# Sheet1.net
KiCad netlist of a schematic drawn in Altium Designer
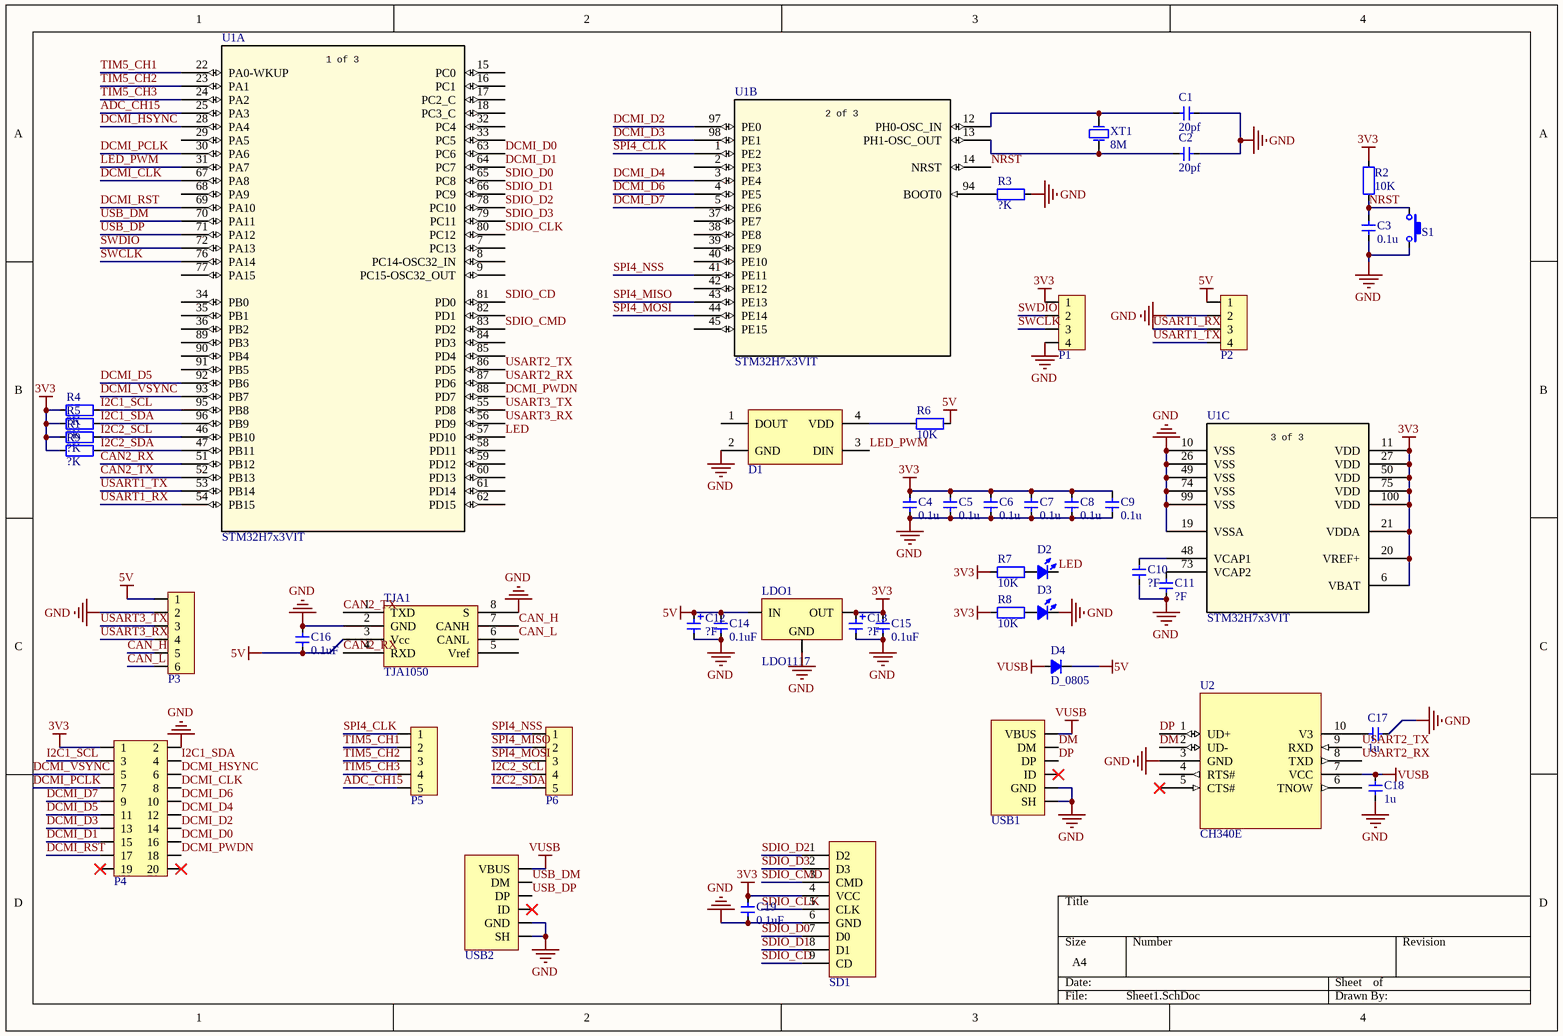
[diagram p0: Sheet1.SchDoc]

(export (version "E")
  (design (tool "Eeschema 10.0.6"))
  (components
    (comp (ref "C1")
      (value "20pf")
      (footprint "PCB_PassiveCap:CAP_0603")
      (description "Capacitor")
      (fields (field (name "Comment") "Cap_0603"))
      (libsource (lib "SCH_Passive") (part "Cap_0603"))
    )
    (comp (ref "C2")
      (value "20pf")
      (footprint "PCB_PassiveCap:CAP_0603")
      (description "Capacitor")
      (fields (field (name "Comment") "Cap_0603"))
      (libsource (lib "SCH_Passive") (part "Cap_0603"))
    )
    (comp (ref "C3")
      (value "0.1u")
      (footprint "PCB_PassiveCap:CAP_0603")
      (description "Capacitor")
      (fields (field (name "Comment") "Cap_0603"))
      (libsource (lib "SCH_Passive") (part "Cap_0603"))
    )
    (comp (ref "C4")
      (value "0.1u")
      (footprint "PCB_PassiveCap:CAP_0603")
      (description "Capacitor")
      (fields (field (name "Comment") "Cap_0603"))
      (libsource (lib "SCH_Passive") (part "Cap_0603"))
    )
    (comp (ref "C5")
      (value "0.1u")
      (footprint "PCB_PassiveCap:CAP_0603")
      (description "Capacitor")
      (fields (field (name "Comment") "Cap_0603"))
      (libsource (lib "SCH_Passive") (part "Cap_0603"))
    )
    (comp (ref "C6")
      (value "0.1u")
      (footprint "PCB_PassiveCap:CAP_0603")
      (description "Capacitor")
      (fields (field (name "Comment") "Cap_0603"))
      (libsource (lib "SCH_Passive") (part "Cap_0603"))
    )
    (comp (ref "C7")
      (value "0.1u")
      (footprint "PCB_PassiveCap:CAP_0603")
      (description "Capacitor")
      (fields (field (name "Comment") "Cap_0603"))
      (libsource (lib "SCH_Passive") (part "Cap_0603"))
    )
    (comp (ref "C8")
      (value "0.1u")
      (footprint "PCB_PassiveCap:CAP_0603")
      (description "Capacitor")
      (fields (field (name "Comment") "Cap_0603"))
      (libsource (lib "SCH_Passive") (part "Cap_0603"))
    )
    (comp (ref "C9")
      (value "0.1u")
      (footprint "PCB_PassiveCap:CAP_0603")
      (description "Capacitor")
      (fields (field (name "Comment") "Cap_0603"))
      (libsource (lib "SCH_Passive") (part "Cap_0603"))
    )
    (comp (ref "C10")
      (value "?F")
      (footprint "PCB_PassiveCap:CAP_0603")
      (description "Capacitor")
      (fields (field (name "Comment") "Cap_0603"))
      (libsource (lib "SCH_Passive") (part "Cap_0603"))
    )
    (comp (ref "C11")
      (value "?F")
      (footprint "PCB_PassiveCap:CAP_0603")
      (description "Capacitor")
      (fields (field (name "Comment") "Cap_0603"))
      (libsource (lib "SCH_Passive") (part "Cap_0603"))
    )
    (comp (ref "C12")
      (value "?F")
      (footprint "PCB_PassiveCap:CAP_TAN_A1206")
      (description "Capacitor")
      (fields (field (name "Comment") "Cap_Tan_1206"))
      (libsource (lib "SCH_Passive") (part "Cap_Tan_1206"))
    )
    (comp (ref "C13")
      (value "?F")
      (footprint "PCB_PassiveCap:CAP_TAN_A1206")
      (description "Capacitor")
      (fields (field (name "Comment") "Cap_Tan_1206"))
      (libsource (lib "SCH_Passive") (part "Cap_Tan_1206"))
    )
    (comp (ref "C14")
      (value "0.1uF")
      (footprint "PCB_PassiveCap:CAP_0603")
      (description "Capacitor")
      (fields (field (name "Comment") "Cap_0603"))
      (libsource (lib "SCH_Passive") (part "Cap_0603"))
    )
    (comp (ref "C15")
      (value "0.1uF")
      (footprint "PCB_PassiveCap:CAP_0603")
      (description "Capacitor")
      (fields (field (name "Comment") "Cap_0603"))
      (libsource (lib "SCH_Passive") (part "Cap_0603"))
    )
    (comp (ref "C16")
      (value "0.1uF")
      (footprint "PCB_PassiveCap:CAP_0603")
      (description "Capacitor")
      (fields (field (name "Comment") "Cap_0603"))
      (libsource (lib "SCH_Passive") (part "Cap_0603"))
    )
    (comp (ref "C17")
      (value "1u")
      (footprint "PCB_PassiveCap:CAP_0603")
      (description "Capacitor")
      (fields (field (name "Comment") "Cap_0603"))
      (libsource (lib "SCH_Passive") (part "Cap_0603"))
    )
    (comp (ref "C18")
      (value "1u")
      (footprint "PCB_PassiveCap:CAP_0603")
      (description "Capacitor")
      (fields (field (name "Comment") "Cap_0603"))
      (libsource (lib "SCH_Passive") (part "Cap_0603"))
    )
    (comp (ref "C19")
      (value "0.1uF")
      (footprint "PCB_PassiveCap:CAP_0603")
      (description "Capacitor")
      (fields (field (name "Comment") "Cap_0603"))
      (libsource (lib "SCH_Passive") (part "Cap_0603"))
    )
    (comp (ref "D1")
      (value "LED_3535_SK6812")
      (footprint "PCB_ActiveLED:LED_3535_4P")
      (description "LED")
      (libsource (lib "SCH_Active") (part "LED_3535_SK6812"))
    )
    (comp (ref "D2")
      (value "LED_0805")
      (footprint "PCB_ActiveLED:LED_0805_RED")
      (description "LED")
      (libsource (lib "SCH_Active") (part "LED_0805"))
    )
    (comp (ref "D3")
      (value "LED_0805")
      (footprint "PCB_ActiveLED:LED_0805_RED")
      (description "LED")
      (libsource (lib "SCH_Active") (part "LED_0805"))
    )
    (comp (ref "D4")
      (value "D_0805")
      (footprint "LED_0805_YELLOW")
      (libsource (lib "SCH_Active") (part "D_0805"))
    )
    (comp (ref "LDO1")
      (value "LDO1117")
      (footprint "PCB_IntegratedCircuit:SOT223-3")
      (description "Power")
      (libsource (lib "SCH_IntegratedCircuit") (part "LDO1117"))
    )
    (comp (ref "P1")
      (value "HDR1x4_2.54")
      (footprint "PCB_ConnectorHDR:HDR1x4_2.54_180")
      (description "Header")
      (libsource (lib "SCH_ConnectorHDR") (part "HDR1x4_2.54"))
    )
    (comp (ref "P2")
      (value "HDR1x4_2.54")
      (footprint "PCB_ConnectorHDR:HDR1x4_2.54_180")
      (description "Header")
      (libsource (lib "SCH_ConnectorHDR") (part "HDR1x4_2.54"))
    )
    (comp (ref "P3")
      (value "HDR1x6_2.54")
      (footprint "PCB_ConnectorHDR:HDR1X6_2.54_180")
      (description "Header")
      (libsource (lib "SCH_ConnectorHDR") (part "HDR1x6_2.54"))
    )
    (comp (ref "P4")
      (value "HDR2x10_2.54")
      (footprint "PCB_ConnectorHDR:HDR2X10_2.54_180")
      (description "Header")
      (libsource (lib "SCH_ConnectorHDR") (part "HDR2x10_2.54"))
    )
    (comp (ref "P5")
      (value "HDR1x5_2.54")
      (footprint "PCB_ConnectorHDR:HDR1X5_2.54_180")
      (description "Header")
      (libsource (lib "SCH_ConnectorHDR") (part "HDR1x5_2.54"))
    )
    (comp (ref "P6")
      (value "HDR1x5_2.54")
      (footprint "PCB_ConnectorHDR:HDR1X5_2.54_180")
      (description "Header")
      (libsource (lib "SCH_ConnectorHDR") (part "HDR1x5_2.54"))
    )
    (comp (ref "R1")
      (value "?K")
      (footprint "PCB_PassiveRes:RES_0603")
      (description "Resistor")
      (fields (field (name "Comment") "Res_0603"))
      (libsource (lib "SCH_Passive") (part "Res_0603"))
    )
    (comp (ref "R2")
      (value "10K")
      (footprint "PCB_PassiveRes:RES_0603")
      (description "Resistor")
      (fields (field (name "Comment") "Res_0603"))
      (libsource (lib "") (part "Res_0603_1"))
    )
    (comp (ref "R3")
      (value "?K")
      (footprint "PCB_PassiveRes:RES_0603")
      (description "Resistor")
      (fields (field (name "Comment") "Res_0603"))
      (libsource (lib "SCH_Passive") (part "Res_0603"))
    )
    (comp (ref "R4")
      (value "?K")
      (footprint "PCB_PassiveRes:RES_0603")
      (description "Resistor")
      (fields (field (name "Comment") "Res_0603"))
      (libsource (lib "SCH_Passive") (part "Res_0603"))
    )
    (comp (ref "R5")
      (value "?K")
      (footprint "PCB_PassiveRes:RES_0603")
      (description "Resistor")
      (fields (field (name "Comment") "Res_0603"))
      (libsource (lib "SCH_Passive") (part "Res_0603"))
    )
    (comp (ref "R6")
      (value "10K")
      (footprint "PCB_PassiveRes:RES_0603")
      (description "Resistor")
      (fields (field (name "Comment") "Res_0603"))
      (libsource (lib "SCH_Passive") (part "Res_0603"))
    )
    (comp (ref "R7")
      (value "10K")
      (footprint "PCB_PassiveRes:RES_0603")
      (description "Resistor")
      (fields (field (name "Comment") "Res_0603"))
      (libsource (lib "SCH_Passive") (part "Res_0603"))
    )
    (comp (ref "R8")
      (value "10K")
      (footprint "PCB_PassiveRes:RES_0603")
      (description "Resistor")
      (fields (field (name "Comment") "Res_0603"))
      (libsource (lib "SCH_Passive") (part "Res_0603"))
    )
    (comp (ref "R9")
      (value "?K")
      (footprint "PCB_PassiveRes:RES_0603")
      (description "Resistor")
      (fields (field (name "Comment") "Res_0603"))
      (libsource (lib "SCH_Passive") (part "Res_0603"))
    )
    (comp (ref "S1")
      (value "ButtonTACT_3x4x2_180")
      (footprint "PCB_Switch:ButtonTACT_3x4x2_180H")
      (description "Button")
      (libsource (lib "SCH_Switch") (part "ButtonTACT_3x4x2_180"))
    )
    (comp (ref "SD1")
      (value "SD_Card_TF")
      (footprint "PCB_SDCard:SD_Card_TF")
      (description "SD")
      (libsource (lib "SCH_SDCard") (part "SD_Card_TF"))
    )
    (comp (ref "TJA1")
      (value "TJA1050")
      (footprint "SOP_E150_8")
      (libsource (lib "SCH_IntegratedCircuit") (part "TJA1050"))
    )
    (comp (ref "U1")
      (value "STM32H7x3VIT")
      (footprint "STM32H743VIT")
      (description "Imported")
      (fields
        (field (name "MANUFACTURER_PART_NUMBER") "stm32h7x3vit")
        (field (name "COPYRIGHT") "Copyright (C) 2016 Accelerated Designs. All rights reserved")
      )
      (libsource (lib "SCH_IntegratedCircuit") (part "STM32H7x3VIT"))
    )
    (comp (ref "U2")
      (value "CH340E")
      (footprint "MSOP10")
      (description "USB to TTL Serial / UART")
      (libsource (lib "*") (part "CH340E"))
    )
    (comp (ref "USB1")
      (value "USB_Micro")
      (footprint "PCB_USB:USB_Micro-AB")
      (description "USB")
      (libsource (lib "SCH_USB") (part "USB_Micro"))
    )
    (comp (ref "USB2")
      (value "USB_Micro")
      (footprint "PCB_USB:USB_Micro-AB")
      (description "USB")
      (libsource (lib "SCH_USB") (part "USB_Micro"))
    )
    (comp (ref "XT1")
      (value "8M")
      (footprint "PCB_Oscillator:XT_5032_2")
      (description "Crystal Oscillator")
      (fields (field (name "Comment") "XTAL_5032_2P"))
      (libsource (lib "SCH_Oscillator") (part "XTAL_5032_2P"))
    )
  )
  (nets
    (net (code "1") (name "/ADC_CH15") (class "Default")
      (node (ref "P5") (pin "5") (pinfunction "5_5") (pintype "passive"))
      (node (ref "U1") (pin "25") (pinfunction "PA3_25") (pintype "bidirectional"))
    )
    (net (code "2") (name "/CAN2_RX") (class "Default")
      (node (ref "TJA1") (pin "4") (pinfunction "RXD_4") (pintype "passive"))
      (node (ref "U1") (pin "51") (pinfunction "PB12_51") (pintype "bidirectional"))
    )
    (net (code "3") (name "/CAN2_TX") (class "Default")
      (node (ref "TJA1") (pin "1") (pinfunction "TXD_1") (pintype "passive"))
      (node (ref "U1") (pin "52") (pinfunction "PB13_52") (pintype "bidirectional"))
    )
    (net (code "4") (name "/CAN_H") (class "Default")
      (node (ref "P3") (pin "5") (pinfunction "5_5") (pintype "passive"))
      (node (ref "TJA1") (pin "7") (pinfunction "CANH_7") (pintype "passive"))
    )
    (net (code "5") (name "/CAN_L") (class "Default")
      (node (ref "P3") (pin "6") (pinfunction "6_6") (pintype "passive"))
      (node (ref "TJA1") (pin "6") (pinfunction "CANL_6") (pintype "passive"))
    )
    (net (code "6") (name "/DCMI_CLK") (class "Default")
      (node (ref "P4") (pin "8") (pinfunction "8_8") (pintype "passive"))
      (node (ref "U1") (pin "67") (pinfunction "PA8_67") (pintype "bidirectional"))
    )
    (net (code "7") (name "/DCMI_D0") (class "Default")
      (node (ref "P4") (pin "16") (pinfunction "16_16") (pintype "passive"))
      (node (ref "U1") (pin "63") (pinfunction "PC6_63") (pintype "bidirectional"))
    )
    (net (code "8") (name "/DCMI_D1") (class "Default")
      (node (ref "P4") (pin "15") (pinfunction "15_15") (pintype "passive"))
      (node (ref "U1") (pin "64") (pinfunction "PC7_64") (pintype "bidirectional"))
    )
    (net (code "9") (name "/DCMI_D2") (class "Default")
      (node (ref "P4") (pin "14") (pinfunction "14_14") (pintype "passive"))
      (node (ref "U1") (pin "97") (pinfunction "PE0_97") (pintype "bidirectional"))
    )
    (net (code "10") (name "/DCMI_D3") (class "Default")
      (node (ref "P4") (pin "13") (pinfunction "13_13") (pintype "passive"))
      (node (ref "U1") (pin "98") (pinfunction "PE1_98") (pintype "bidirectional"))
    )
    (net (code "11") (name "/DCMI_D4") (class "Default")
      (node (ref "P4") (pin "12") (pinfunction "12_12") (pintype "passive"))
      (node (ref "U1") (pin "3") (pinfunction "PE4_3") (pintype "bidirectional"))
    )
    (net (code "12") (name "/DCMI_D5") (class "Default")
      (node (ref "P4") (pin "11") (pinfunction "11_11") (pintype "passive"))
      (node (ref "U1") (pin "92") (pinfunction "PB6_92") (pintype "bidirectional"))
    )
    (net (code "13") (name "/DCMI_D6") (class "Default")
      (node (ref "P4") (pin "10") (pinfunction "10_10") (pintype "passive"))
      (node (ref "U1") (pin "4") (pinfunction "PE5_4") (pintype "bidirectional"))
    )
    (net (code "14") (name "/DCMI_D7") (class "Default")
      (node (ref "P4") (pin "9") (pinfunction "9_9") (pintype "passive"))
      (node (ref "U1") (pin "5") (pinfunction "PE6_5") (pintype "bidirectional"))
    )
    (net (code "15") (name "/DCMI_HSYNC") (class "Default")
      (node (ref "P4") (pin "6") (pinfunction "6_6") (pintype "passive"))
      (node (ref "U1") (pin "28") (pinfunction "PA4_28") (pintype "bidirectional"))
    )
    (net (code "16") (name "/DCMI_PCLK") (class "Default")
      (node (ref "P4") (pin "7") (pinfunction "7_7") (pintype "passive"))
      (node (ref "U1") (pin "30") (pinfunction "PA6_30") (pintype "bidirectional"))
    )
    (net (code "17") (name "/DCMI_PWDN") (class "Default")
      (node (ref "P4") (pin "18") (pinfunction "18_18") (pintype "passive"))
      (node (ref "U1") (pin "88") (pinfunction "PD7_88") (pintype "bidirectional"))
    )
    (net (code "18") (name "/DCMI_RST") (class "Default")
      (node (ref "P4") (pin "17") (pinfunction "17_17") (pintype "passive"))
      (node (ref "U1") (pin "69") (pinfunction "PA10_69") (pintype "bidirectional"))
    )
    (net (code "19") (name "/DCMI_VSYNC") (class "Default")
      (node (ref "P4") (pin "5") (pinfunction "5_5") (pintype "passive"))
      (node (ref "U1") (pin "93") (pinfunction "PB7_93") (pintype "bidirectional"))
    )
    (net (code "20") (name "/DM") (class "Default")
      (node (ref "U2") (pin "2") (pinfunction "UD-_2") (pintype "bidirectional"))
      (node (ref "USB1") (pin "2") (pinfunction "DM_2") (pintype "passive"))
    )
    (net (code "21") (name "/DP") (class "Default")
      (node (ref "U2") (pin "1") (pinfunction "UD+_1") (pintype "bidirectional"))
      (node (ref "USB1") (pin "3") (pinfunction "DP_3") (pintype "passive"))
    )
    (net (code "22") (name "/I2C1_SCL") (class "Default")
      (node (ref "P4") (pin "3") (pinfunction "3_3") (pintype "passive"))
      (node (ref "R4") (pin "2") (pinfunction "2_2") (pintype "passive"))
      (node (ref "U1") (pin "95") (pinfunction "PB8_95") (pintype "bidirectional"))
    )
    (net (code "23") (name "/I2C1_SDA") (class "Default")
      (node (ref "P4") (pin "4") (pinfunction "4_4") (pintype "passive"))
      (node (ref "R5") (pin "2") (pinfunction "2_2") (pintype "passive"))
      (node (ref "U1") (pin "96") (pinfunction "PB9_96") (pintype "bidirectional"))
    )
    (net (code "24") (name "/I2C2_SCL") (class "Default")
      (node (ref "P6") (pin "4") (pinfunction "4_4") (pintype "passive"))
      (node (ref "R1") (pin "2") (pinfunction "2_2") (pintype "passive"))
      (node (ref "U1") (pin "46") (pinfunction "PB10_46") (pintype "bidirectional"))
    )
    (net (code "25") (name "/I2C2_SDA") (class "Default")
      (node (ref "P6") (pin "5") (pinfunction "5_5") (pintype "passive"))
      (node (ref "R9") (pin "2") (pinfunction "2_2") (pintype "passive"))
      (node (ref "U1") (pin "47") (pinfunction "PB11_47") (pintype "bidirectional"))
    )
    (net (code "26") (name "/LED") (class "Default")
      (node (ref "D2") (pin "2") (pinfunction "K_2") (pintype "passive"))
      (node (ref "U1") (pin "57") (pinfunction "PD10_57") (pintype "bidirectional"))
    )
    (net (code "27") (name "/LED_PWM") (class "Default")
      (node (ref "D1") (pin "3") (pinfunction "DIN_3") (pintype "passive"))
      (node (ref "U1") (pin "31") (pinfunction "PA7_31") (pintype "bidirectional"))
    )
    (net (code "28") (name "/NRST") (class "Default")
      (node (ref "C3") (pin "2") (pinfunction "2_2") (pintype "passive"))
      (node (ref "R2") (pin "2") (pinfunction "2_2") (pintype "passive"))
      (node (ref "S1") (pin "1") (pinfunction "1_1") (pintype "passive"))
      (node (ref "U1") (pin "14") (pinfunction "NRST_14") (pintype "bidirectional"))
    )
    (net (code "29") (name "/SDIO_CD") (class "Default")
      (node (ref "SD1") (pin "9") (pinfunction "CD_9") (pintype "passive"))
      (node (ref "U1") (pin "81") (pinfunction "PD0_81") (pintype "bidirectional"))
    )
    (net (code "30") (name "/SDIO_CLK") (class "Default")
      (node (ref "SD1") (pin "5") (pinfunction "CLK_5") (pintype "passive"))
      (node (ref "U1") (pin "80") (pinfunction "PC12_80") (pintype "bidirectional"))
    )
    (net (code "31") (name "/SDIO_CMD") (class "Default")
      (node (ref "SD1") (pin "3") (pinfunction "CMD_3") (pintype "passive"))
      (node (ref "U1") (pin "83") (pinfunction "PD2_83") (pintype "bidirectional"))
    )
    (net (code "32") (name "/SDIO_D0") (class "Default")
      (node (ref "SD1") (pin "7") (pinfunction "D0_7") (pintype "passive"))
      (node (ref "U1") (pin "65") (pinfunction "PC8_65") (pintype "bidirectional"))
    )
    (net (code "33") (name "/SDIO_D1") (class "Default")
      (node (ref "SD1") (pin "8") (pinfunction "D1_8") (pintype "passive"))
      (node (ref "U1") (pin "66") (pinfunction "PC9_66") (pintype "bidirectional"))
    )
    (net (code "34") (name "/SDIO_D2") (class "Default")
      (node (ref "SD1") (pin "1") (pinfunction "D2_1") (pintype "passive"))
      (node (ref "U1") (pin "78") (pinfunction "PC10_78") (pintype "bidirectional"))
    )
    (net (code "35") (name "/SDIO_D3") (class "Default")
      (node (ref "SD1") (pin "2") (pinfunction "D3_2") (pintype "passive"))
      (node (ref "U1") (pin "79") (pinfunction "PC11_79") (pintype "bidirectional"))
    )
    (net (code "36") (name "/SPI4_CLK") (class "Default")
      (node (ref "P5") (pin "1") (pinfunction "1_1") (pintype "passive"))
      (node (ref "U1") (pin "1") (pinfunction "PE2_1") (pintype "bidirectional"))
    )
    (net (code "37") (name "/SPI4_MISO") (class "Default")
      (node (ref "P6") (pin "2") (pinfunction "2_2") (pintype "passive"))
      (node (ref "U1") (pin "43") (pinfunction "PE13_43") (pintype "bidirectional"))
    )
    (net (code "38") (name "/SPI4_MOSI") (class "Default")
      (node (ref "P6") (pin "3") (pinfunction "3_3") (pintype "passive"))
      (node (ref "U1") (pin "44") (pinfunction "PE14_44") (pintype "bidirectional"))
    )
    (net (code "39") (name "/SPI4_NSS") (class "Default")
      (node (ref "P6") (pin "1") (pinfunction "1_1") (pintype "passive"))
      (node (ref "U1") (pin "41") (pinfunction "PE11_41") (pintype "bidirectional"))
    )
    (net (code "40") (name "/SWCLK") (class "Default")
      (node (ref "P1") (pin "3") (pinfunction "3_3") (pintype "passive"))
      (node (ref "U1") (pin "76") (pinfunction "PA14_76") (pintype "bidirectional"))
    )
    (net (code "41") (name "/SWDIO") (class "Default")
      (node (ref "P1") (pin "2") (pinfunction "2_2") (pintype "passive"))
      (node (ref "U1") (pin "72") (pinfunction "PA13_72") (pintype "bidirectional"))
    )
    (net (code "42") (name "/TIM5_CH1") (class "Default")
      (node (ref "P5") (pin "2") (pinfunction "2_2") (pintype "passive"))
      (node (ref "U1") (pin "22") (pinfunction "PA0-WKUP_22") (pintype "bidirectional"))
    )
    (net (code "43") (name "/TIM5_CH2") (class "Default")
      (node (ref "P5") (pin "3") (pinfunction "3_3") (pintype "passive"))
      (node (ref "U1") (pin "23") (pinfunction "PA1_23") (pintype "bidirectional"))
    )
    (net (code "44") (name "/TIM5_CH3") (class "Default")
      (node (ref "P5") (pin "4") (pinfunction "4_4") (pintype "passive"))
      (node (ref "U1") (pin "24") (pinfunction "PA2_24") (pintype "bidirectional"))
    )
    (net (code "45") (name "/USART1_RX") (class "Default")
      (node (ref "P2") (pin "3") (pinfunction "3_3") (pintype "passive"))
      (node (ref "U1") (pin "54") (pinfunction "PB15_54") (pintype "bidirectional"))
    )
    (net (code "46") (name "/USART1_TX") (class "Default")
      (node (ref "P2") (pin "4") (pinfunction "4_4") (pintype "passive"))
      (node (ref "U1") (pin "53") (pinfunction "PB14_53") (pintype "bidirectional"))
    )
    (net (code "47") (name "/USART2_RX") (class "Default")
      (node (ref "U1") (pin "87") (pinfunction "PD6_87") (pintype "bidirectional"))
      (node (ref "U2") (pin "8") (pinfunction "TXD_8") (pintype "output"))
    )
    (net (code "48") (name "/USART2_TX") (class "Default")
      (node (ref "U1") (pin "86") (pinfunction "PD5_86") (pintype "bidirectional"))
      (node (ref "U2") (pin "9") (pinfunction "RXD_9") (pintype "input"))
    )
    (net (code "49") (name "/USART3_RX") (class "Default")
      (node (ref "P3") (pin "4") (pinfunction "4_4") (pintype "passive"))
      (node (ref "U1") (pin "56") (pinfunction "PD9_56") (pintype "bidirectional"))
    )
    (net (code "50") (name "/USART3_TX") (class "Default")
      (node (ref "P3") (pin "3") (pinfunction "3_3") (pintype "passive"))
      (node (ref "U1") (pin "55") (pinfunction "PD8_55") (pintype "bidirectional"))
    )
    (net (code "51") (name "/USB_DM") (class "Default")
      (node (ref "U1") (pin "70") (pinfunction "PA11_70") (pintype "bidirectional"))
      (node (ref "USB2") (pin "2") (pinfunction "DM_2") (pintype "passive"))
    )
    (net (code "52") (name "/USB_DP") (class "Default")
      (node (ref "U1") (pin "71") (pinfunction "PA12_71") (pintype "bidirectional"))
      (node (ref "USB2") (pin "3") (pinfunction "DP_3") (pintype "passive"))
    )
    (net (code "53") (name "3V3") (class "Default")
      (node (ref "C13") (pin "1") (pinfunction "1_1") (pintype "passive"))
      (node (ref "C15") (pin "2") (pinfunction "2_2") (pintype "passive"))
      (node (ref "C19") (pin "2") (pinfunction "2_2") (pintype "passive"))
      (node (ref "C4") (pin "2") (pinfunction "2_2") (pintype "passive"))
      (node (ref "C5") (pin "2") (pinfunction "2_2") (pintype "passive"))
      (node (ref "C6") (pin "2") (pinfunction "2_2") (pintype "passive"))
      (node (ref "C7") (pin "2") (pinfunction "2_2") (pintype "passive"))
      (node (ref "C8") (pin "2") (pinfunction "2_2") (pintype "passive"))
      (node (ref "C9") (pin "2") (pinfunction "2_2") (pintype "passive"))
      (node (ref "LDO1") (pin "2") (pinfunction "OUT_2") (pintype "power_in"))
      (node (ref "P1") (pin "1") (pinfunction "1_1") (pintype "passive"))
      (node (ref "P4") (pin "1") (pinfunction "1_1") (pintype "passive"))
      (node (ref "R1") (pin "1") (pinfunction "1_1") (pintype "passive"))
      (node (ref "R2") (pin "1") (pinfunction "1_1") (pintype "passive"))
      (node (ref "R4") (pin "1") (pinfunction "1_1") (pintype "passive"))
      (node (ref "R5") (pin "1") (pinfunction "1_1") (pintype "passive"))
      (node (ref "R7") (pin "1") (pinfunction "1_1") (pintype "passive"))
      (node (ref "R8") (pin "1") (pinfunction "1_1") (pintype "passive"))
      (node (ref "R9") (pin "1") (pinfunction "1_1") (pintype "passive"))
      (node (ref "SD1") (pin "4") (pinfunction "VCC_4") (pintype "passive"))
      (node (ref "U1") (pin "100") (pinfunction "VDD_100") (pintype "power_in"))
      (node (ref "U1") (pin "11") (pinfunction "VDD_11") (pintype "power_in"))
      (node (ref "U1") (pin "20") (pinfunction "VREF+_20") (pintype "power_in"))
      (node (ref "U1") (pin "21") (pinfunction "VDDA_21") (pintype "power_in"))
      (node (ref "U1") (pin "27") (pinfunction "VDD_27") (pintype "power_in"))
      (node (ref "U1") (pin "50") (pinfunction "VDD_50") (pintype "power_in"))
      (node (ref "U1") (pin "6") (pinfunction "VBAT_6") (pintype "power_in"))
      (node (ref "U1") (pin "75") (pinfunction "VDD_75") (pintype "power_in"))
    )
    (net (code "54") (name "5V") (class "Default")
      (node (ref "C12") (pin "1") (pinfunction "1_1") (pintype "passive"))
      (node (ref "C14") (pin "2") (pinfunction "2_2") (pintype "passive"))
      (node (ref "C16") (pin "2") (pinfunction "2_2") (pintype "passive"))
      (node (ref "D4") (pin "2") (pinfunction "K_2") (pintype "passive"))
      (node (ref "LDO1") (pin "3") (pinfunction "IN_3") (pintype "power_in"))
      (node (ref "P2") (pin "1") (pinfunction "1_1") (pintype "passive"))
      (node (ref "P3") (pin "1") (pinfunction "1_1") (pintype "passive"))
      (node (ref "R6") (pin "2") (pinfunction "2_2") (pintype "passive"))
      (node (ref "TJA1") (pin "3") (pinfunction "Vcc_3") (pintype "passive"))
    )
    (net (code "55") (name "GND") (class "Default")
      (node (ref "C1") (pin "1") (pinfunction "1_1") (pintype "passive"))
      (node (ref "C10") (pin "1") (pinfunction "1_1") (pintype "passive"))
      (node (ref "C11") (pin "1") (pinfunction "1_1") (pintype "passive"))
      (node (ref "C12") (pin "2") (pinfunction "2_2") (pintype "passive"))
      (node (ref "C13") (pin "2") (pinfunction "2_2") (pintype "passive"))
      (node (ref "C14") (pin "1") (pinfunction "1_1") (pintype "passive"))
      (node (ref "C15") (pin "1") (pinfunction "1_1") (pintype "passive"))
      (node (ref "C16") (pin "1") (pinfunction "1_1") (pintype "passive"))
      (node (ref "C17") (pin "1") (pinfunction "1_1") (pintype "passive"))
      (node (ref "C18") (pin "2") (pinfunction "2_2") (pintype "passive"))
      (node (ref "C19") (pin "1") (pinfunction "1_1") (pintype "passive"))
      (node (ref "C2") (pin "1") (pinfunction "1_1") (pintype "passive"))
      (node (ref "C3") (pin "1") (pinfunction "1_1") (pintype "passive"))
      (node (ref "C4") (pin "1") (pinfunction "1_1") (pintype "passive"))
      (node (ref "C5") (pin "1") (pinfunction "1_1") (pintype "passive"))
      (node (ref "C6") (pin "1") (pinfunction "1_1") (pintype "passive"))
      (node (ref "C7") (pin "1") (pinfunction "1_1") (pintype "passive"))
      (node (ref "C8") (pin "1") (pinfunction "1_1") (pintype "passive"))
      (node (ref "C9") (pin "1") (pinfunction "1_1") (pintype "passive"))
      (node (ref "D1") (pin "2") (pinfunction "GND_2") (pintype "passive"))
      (node (ref "D3") (pin "2") (pinfunction "K_2") (pintype "passive"))
      (node (ref "LDO1") (pin "1") (pinfunction "GND_1") (pintype "power_in"))
      (node (ref "P1") (pin "4") (pinfunction "4_4") (pintype "passive"))
      (node (ref "P2") (pin "2") (pinfunction "2_2") (pintype "passive"))
      (node (ref "P3") (pin "2") (pinfunction "2_2") (pintype "passive"))
      (node (ref "P4") (pin "2") (pinfunction "2_2") (pintype "passive"))
      (node (ref "R3") (pin "2") (pinfunction "2_2") (pintype "passive"))
      (node (ref "S1") (pin "2") (pinfunction "2_2") (pintype "passive"))
      (node (ref "SD1") (pin "6") (pinfunction "GND_6") (pintype "passive"))
      (node (ref "TJA1") (pin "2") (pinfunction "GND_2") (pintype "passive"))
      (node (ref "TJA1") (pin "8") (pinfunction "S_8") (pintype "passive"))
      (node (ref "U1") (pin "10") (pinfunction "VSS_10") (pintype "power_in"))
      (node (ref "U1") (pin "19") (pinfunction "VSSA_19") (pintype "power_in"))
      (node (ref "U1") (pin "26") (pinfunction "VSS_26") (pintype "power_in"))
      (node (ref "U1") (pin "49") (pinfunction "VSS_49") (pintype "power_in"))
      (node (ref "U1") (pin "74") (pinfunction "VSS_74") (pintype "power_in"))
      (node (ref "U1") (pin "99") (pinfunction "VSS_99") (pintype "power_in"))
      (node (ref "U2") (pin "3") (pinfunction "GND_3") (pintype "power_in"))
      (node (ref "USB1") (pin "0") (pinfunction "SH_0") (pintype "passive"))
      (node (ref "USB1") (pin "5") (pinfunction "GND_5") (pintype "passive"))
      (node (ref "USB2") (pin "0") (pinfunction "SH_0") (pintype "passive"))
      (node (ref "USB2") (pin "5") (pinfunction "GND_5") (pintype "passive"))
    )
    (net (code "56") (name "Net-(D1-VDD)") (class "Default")
      (node (ref "D1") (pin "4") (pinfunction "VDD_4") (pintype "passive"))
      (node (ref "R6") (pin "1") (pinfunction "1_1") (pintype "passive"))
    )
    (net (code "57") (name "Net-(D2-A)") (class "Default")
      (node (ref "D2") (pin "1") (pinfunction "A_1") (pintype "passive"))
      (node (ref "R7") (pin "2") (pinfunction "2_2") (pintype "passive"))
    )
    (net (code "58") (name "Net-(D3-A)") (class "Default")
      (node (ref "D3") (pin "1") (pinfunction "A_1") (pintype "passive"))
      (node (ref "R8") (pin "2") (pinfunction "2_2") (pintype "passive"))
    )
    (net (code "59") (name "Net-(U1B-BOOT0)") (class "Default")
      (node (ref "R3") (pin "1") (pinfunction "1_1") (pintype "passive"))
      (node (ref "U1") (pin "94") (pinfunction "BOOT0_94") (pintype "input"))
    )
    (net (code "60") (name "Net-(U1B-PH0-OSC_IN)") (class "Default")
      (node (ref "C1") (pin "2") (pinfunction "2_2") (pintype "passive"))
      (node (ref "U1") (pin "12") (pinfunction "PH0-OSC_IN_12") (pintype "bidirectional"))
      (node (ref "XT1") (pin "2") (pinfunction "OSC2_2") (pintype "passive"))
    )
    (net (code "61") (name "Net-(U1B-PH1-OSC_OUT)") (class "Default")
      (node (ref "C2") (pin "2") (pinfunction "2_2") (pintype "passive"))
      (node (ref "U1") (pin "13") (pinfunction "PH1-OSC_OUT_13") (pintype "bidirectional"))
      (node (ref "XT1") (pin "1") (pinfunction "OSC1_1") (pintype "passive"))
    )
    (net (code "62") (name "Net-(U1C-VCAP1)") (class "Default")
      (node (ref "C10") (pin "2") (pinfunction "2_2") (pintype "passive"))
      (node (ref "U1") (pin "48") (pinfunction "VCAP1_48") (pintype "power_in"))
    )
    (net (code "63") (name "Net-(U1C-VCAP2)") (class "Default")
      (node (ref "C11") (pin "2") (pinfunction "2_2") (pintype "passive"))
      (node (ref "U1") (pin "73") (pinfunction "VCAP2_73") (pintype "power_in"))
    )
    (net (code "64") (name "Net-(U2-V3)") (class "Default")
      (node (ref "C17") (pin "2") (pinfunction "2_2") (pintype "passive"))
      (node (ref "U2") (pin "10") (pinfunction "V3_10") (pintype "power_in"))
    )
    (net (code "65") (name "VUSB") (class "Default")
      (node (ref "C18") (pin "1") (pinfunction "1_1") (pintype "passive"))
      (node (ref "D4") (pin "1") (pinfunction "A_1") (pintype "passive"))
      (node (ref "U2") (pin "7") (pinfunction "VCC_7") (pintype "power_in"))
      (node (ref "USB1") (pin "1") (pinfunction "VBUS_1") (pintype "passive"))
      (node (ref "USB2") (pin "1") (pinfunction "VBUS_1") (pintype "passive"))
    )
    (net (code "66") (name "unconnected-(D1-DOUT-Pad1)") (class "Default")
      (node (ref "D1") (pin "1") (pinfunction "DOUT_1") (pintype "passive"))
    )
    (net (code "67") (name "unconnected-(P4-Pad19)") (class "Default")
      (node (ref "P4") (pin "19") (pinfunction "19_19") (pintype "passive+no_connect"))
    )
    (net (code "68") (name "unconnected-(P4-Pad20)") (class "Default")
      (node (ref "P4") (pin "20") (pinfunction "20_20") (pintype "passive+no_connect"))
    )
    (net (code "69") (name "unconnected-(TJA1-Vref-Pad5)") (class "Default")
      (node (ref "TJA1") (pin "5") (pinfunction "Vref_5") (pintype "passive"))
    )
    (net (code "70") (name "unconnected-(U1A-PA5-Pad29)") (class "Default")
      (node (ref "U1") (pin "29") (pinfunction "PA5_29") (pintype "bidirectional"))
    )
    (net (code "71") (name "unconnected-(U1A-PA9-Pad68)") (class "Default")
      (node (ref "U1") (pin "68") (pinfunction "PA9_68") (pintype "bidirectional"))
    )
    (net (code "72") (name "unconnected-(U1A-PA15-Pad77)") (class "Default")
      (node (ref "U1") (pin "77") (pinfunction "PA15_77") (pintype "bidirectional"))
    )
    (net (code "73") (name "unconnected-(U1A-PB0-Pad34)") (class "Default")
      (node (ref "U1") (pin "34") (pinfunction "PB0_34") (pintype "bidirectional"))
    )
    (net (code "74") (name "unconnected-(U1A-PB1-Pad35)") (class "Default")
      (node (ref "U1") (pin "35") (pinfunction "PB1_35") (pintype "bidirectional"))
    )
    (net (code "75") (name "unconnected-(U1A-PB2-Pad36)") (class "Default")
      (node (ref "U1") (pin "36") (pinfunction "PB2_36") (pintype "bidirectional"))
    )
    (net (code "76") (name "unconnected-(U1A-PB3-Pad89)") (class "Default")
      (node (ref "U1") (pin "89") (pinfunction "PB3_89") (pintype "bidirectional"))
    )
    (net (code "77") (name "unconnected-(U1A-PB4-Pad90)") (class "Default")
      (node (ref "U1") (pin "90") (pinfunction "PB4_90") (pintype "bidirectional"))
    )
    (net (code "78") (name "unconnected-(U1A-PB5-Pad91)") (class "Default")
      (node (ref "U1") (pin "91") (pinfunction "PB5_91") (pintype "bidirectional"))
    )
    (net (code "79") (name "unconnected-(U1A-PC0-Pad15)") (class "Default")
      (node (ref "U1") (pin "15") (pinfunction "PC0_15") (pintype "bidirectional"))
    )
    (net (code "80") (name "unconnected-(U1A-PC1-Pad16)") (class "Default")
      (node (ref "U1") (pin "16") (pinfunction "PC1_16") (pintype "bidirectional"))
    )
    (net (code "81") (name "unconnected-(U1A-PC2_C-Pad17)") (class "Default")
      (node (ref "U1") (pin "17") (pinfunction "PC2_C_17") (pintype "bidirectional"))
    )
    (net (code "82") (name "unconnected-(U1A-PC3_C-Pad18)") (class "Default")
      (node (ref "U1") (pin "18") (pinfunction "PC3_C_18") (pintype "bidirectional"))
    )
    (net (code "83") (name "unconnected-(U1A-PC4-Pad32)") (class "Default")
      (node (ref "U1") (pin "32") (pinfunction "PC4_32") (pintype "bidirectional"))
    )
    (net (code "84") (name "unconnected-(U1A-PC5-Pad33)") (class "Default")
      (node (ref "U1") (pin "33") (pinfunction "PC5_33") (pintype "bidirectional"))
    )
    (net (code "85") (name "unconnected-(U1A-PC13-Pad7)") (class "Default")
      (node (ref "U1") (pin "7") (pinfunction "PC13_7") (pintype "bidirectional"))
    )
    (net (code "86") (name "unconnected-(U1A-PC14-OSC32_IN-Pad8)") (class "Default")
      (node (ref "U1") (pin "8") (pinfunction "PC14-OSC32_IN_8") (pintype "bidirectional"))
    )
    (net (code "87") (name "unconnected-(U1A-PC15-OSC32_OUT-Pad9)") (class "Default")
      (node (ref "U1") (pin "9") (pinfunction "PC15-OSC32_OUT_9") (pintype "bidirectional"))
    )
    (net (code "88") (name "unconnected-(U1A-PD1-Pad82)") (class "Default")
      (node (ref "U1") (pin "82") (pinfunction "PD1_82") (pintype "bidirectional"))
    )
    (net (code "89") (name "unconnected-(U1A-PD3-Pad84)") (class "Default")
      (node (ref "U1") (pin "84") (pinfunction "PD3_84") (pintype "bidirectional"))
    )
    (net (code "90") (name "unconnected-(U1A-PD4-Pad85)") (class "Default")
      (node (ref "U1") (pin "85") (pinfunction "PD4_85") (pintype "bidirectional"))
    )
    (net (code "91") (name "unconnected-(U1A-PD11-Pad58)") (class "Default")
      (node (ref "U1") (pin "58") (pinfunction "PD11_58") (pintype "bidirectional"))
    )
    (net (code "92") (name "unconnected-(U1A-PD12-Pad59)") (class "Default")
      (node (ref "U1") (pin "59") (pinfunction "PD12_59") (pintype "bidirectional"))
    )
    (net (code "93") (name "unconnected-(U1A-PD13-Pad60)") (class "Default")
      (node (ref "U1") (pin "60") (pinfunction "PD13_60") (pintype "bidirectional"))
    )
    (net (code "94") (name "unconnected-(U1A-PD14-Pad61)") (class "Default")
      (node (ref "U1") (pin "61") (pinfunction "PD14_61") (pintype "bidirectional"))
    )
    (net (code "95") (name "unconnected-(U1A-PD15-Pad62)") (class "Default")
      (node (ref "U1") (pin "62") (pinfunction "PD15_62") (pintype "bidirectional"))
    )
    (net (code "96") (name "unconnected-(U1B-PE3-Pad2)") (class "Default")
      (node (ref "U1") (pin "2") (pinfunction "PE3_2") (pintype "bidirectional"))
    )
    (net (code "97") (name "unconnected-(U1B-PE7-Pad37)") (class "Default")
      (node (ref "U1") (pin "37") (pinfunction "PE7_37") (pintype "bidirectional"))
    )
    (net (code "98") (name "unconnected-(U1B-PE8-Pad38)") (class "Default")
      (node (ref "U1") (pin "38") (pinfunction "PE8_38") (pintype "bidirectional"))
    )
    (net (code "99") (name "unconnected-(U1B-PE9-Pad39)") (class "Default")
      (node (ref "U1") (pin "39") (pinfunction "PE9_39") (pintype "bidirectional"))
    )
    (net (code "100") (name "unconnected-(U1B-PE10-Pad40)") (class "Default")
      (node (ref "U1") (pin "40") (pinfunction "PE10_40") (pintype "bidirectional"))
    )
    (net (code "101") (name "unconnected-(U1B-PE12-Pad42)") (class "Default")
      (node (ref "U1") (pin "42") (pinfunction "PE12_42") (pintype "bidirectional"))
    )
    (net (code "102") (name "unconnected-(U1B-PE15-Pad45)") (class "Default")
      (node (ref "U1") (pin "45") (pinfunction "PE15_45") (pintype "bidirectional"))
    )
    (net (code "103") (name "unconnected-(U2-CTS#-Pad5)") (class "Default")
      (node (ref "U2") (pin "5") (pinfunction "CTS#_5") (pintype "input+no_connect"))
    )
    (net (code "104") (name "unconnected-(U2-RTS#-Pad4)") (class "Default")
      (node (ref "U2") (pin "4") (pinfunction "RTS#_4") (pintype "output"))
    )
    (net (code "105") (name "unconnected-(U2-TNOW-Pad6)") (class "Default")
      (node (ref "U2") (pin "6") (pinfunction "TNOW_6") (pintype "output"))
    )
    (net (code "106") (name "unconnected-(USB1-ID-Pad4)") (class "Default")
      (node (ref "USB1") (pin "4") (pinfunction "ID_4") (pintype "passive+no_connect"))
    )
    (net (code "107") (name "unconnected-(USB2-ID-Pad4)") (class "Default")
      (node (ref "USB2") (pin "4") (pinfunction "ID_4") (pintype "passive+no_connect"))
    )
  )
)
